# LTC6804-2_8S_TR-2512.net
KiCad netlist of a schematic drawn in Altium Designer
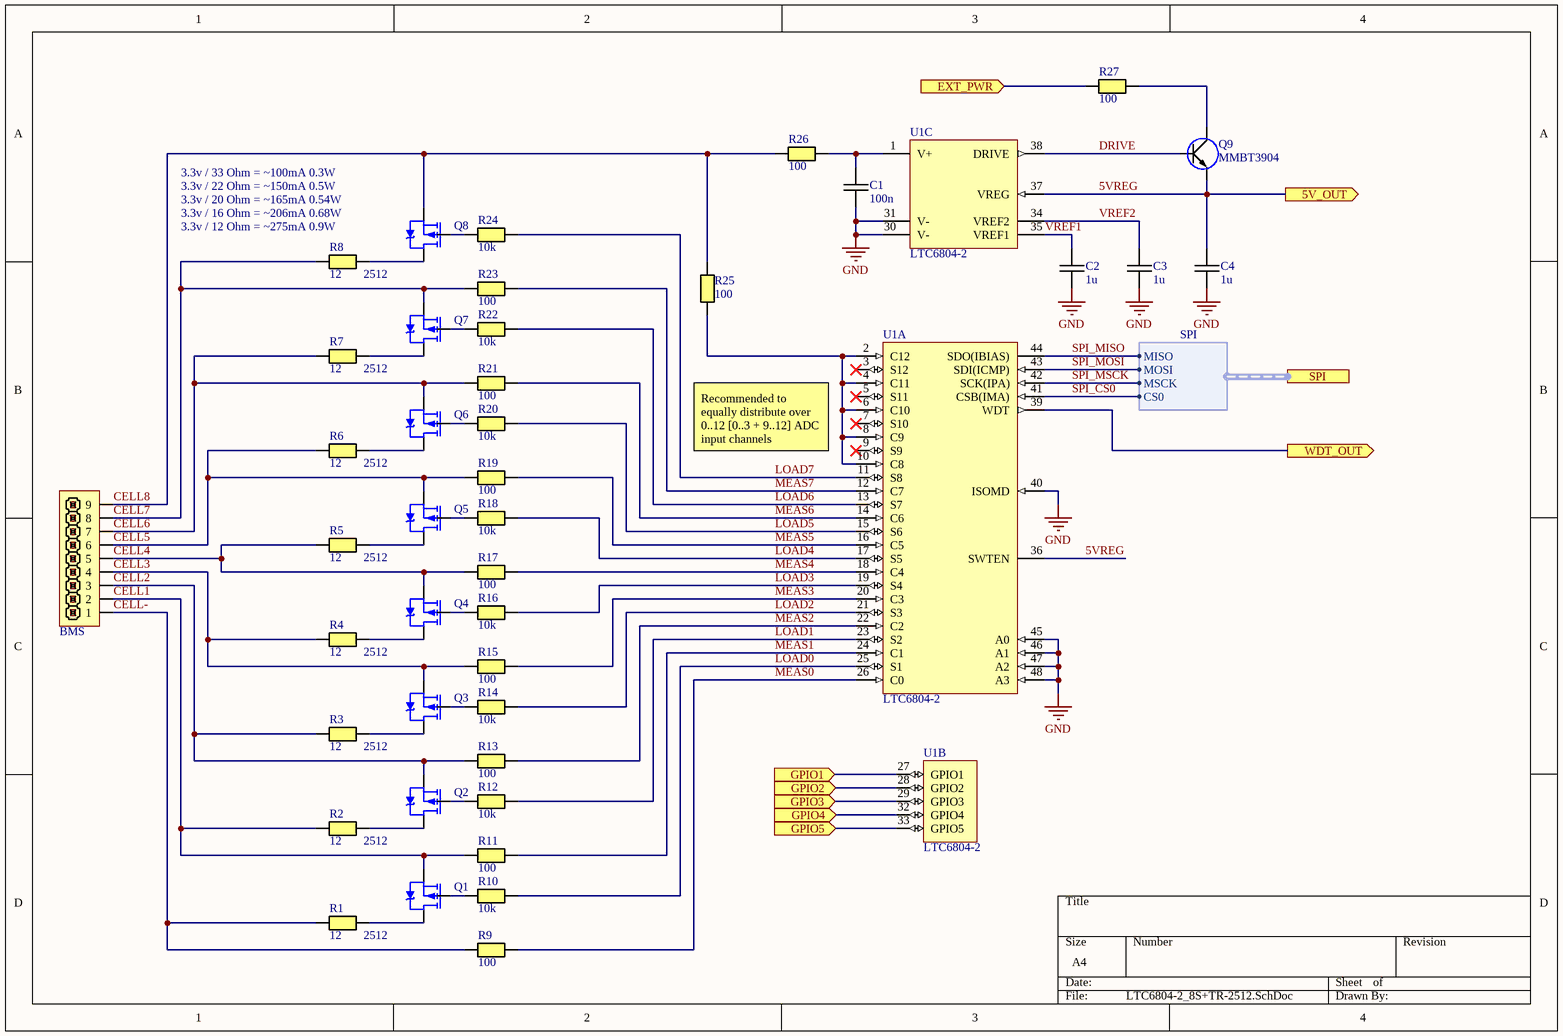
[diagram p0: LTC6804-2_8S+TR-2512.SchDoc]

(export (version "E")
  (design (tool "Eeschema 10.0.6"))
  (components
    (comp (ref "BMS")
      (value "PIN HEADER 1x9")
      (footprint "XH2.54 9P")
      (libsource (lib "Connectors") (part "PIN HEADER 2.54 1x9"))
    )
    (comp (ref "C1")
      (value "100n")
      (footprint "CAPC0603(1608)55_N")
      (description "Ceramic capacitor Medium density")
      (libsource (lib "Discrete") (part "Capacitor M"))
    )
    (comp (ref "C2")
      (value "1u")
      (footprint "CAPC0805(2012)75_N")
      (description "Ceramic capacitor Medium density")
      (libsource (lib "Discrete") (part "Capacitor M"))
    )
    (comp (ref "C3")
      (value "1u")
      (footprint "CAPC0805(2012)75_N")
      (description "Ceramic capacitor Medium density")
      (libsource (lib "Discrete") (part "Capacitor M"))
    )
    (comp (ref "C4")
      (value "1u")
      (footprint "CAPC0805(2012)75_N")
      (description "Ceramic capacitor Medium density")
      (libsource (lib "Discrete") (part "Capacitor M"))
    )
    (comp (ref "Q1")
      (value "BSS308PE")
      (footprint "SOT23")
      (description "OptiMOS™ P3 Small-Signal-Transistor")
      (libsource (lib "Transistors") (part "BSS308PE"))
    )
    (comp (ref "Q2")
      (value "BSS308PE")
      (footprint "SOT23")
      (description "OptiMOS™ P3 Small-Signal-Transistor")
      (libsource (lib "Transistors") (part "BSS308PE"))
    )
    (comp (ref "Q3")
      (value "BSS308PE")
      (footprint "SOT23")
      (description "OptiMOS™ P3 Small-Signal-Transistor")
      (libsource (lib "Transistors") (part "BSS308PE"))
    )
    (comp (ref "Q4")
      (value "BSS308PE")
      (footprint "SOT23")
      (description "OptiMOS™ P3 Small-Signal-Transistor")
      (libsource (lib "Transistors") (part "BSS308PE"))
    )
    (comp (ref "Q5")
      (value "BSS308PE")
      (footprint "SOT23")
      (description "OptiMOS™ P3 Small-Signal-Transistor")
      (libsource (lib "Transistors") (part "BSS308PE"))
    )
    (comp (ref "Q6")
      (value "BSS308PE")
      (footprint "SOT23")
      (description "OptiMOS™ P3 Small-Signal-Transistor")
      (libsource (lib "Transistors") (part "BSS308PE"))
    )
    (comp (ref "Q7")
      (value "BSS308PE")
      (footprint "SOT23")
      (description "OptiMOS™ P3 Small-Signal-Transistor")
      (libsource (lib "Transistors") (part "BSS308PE"))
    )
    (comp (ref "Q8")
      (value "BSS308PE")
      (footprint "SOT23")
      (description "OptiMOS™ P3 Small-Signal-Transistor")
      (libsource (lib "Transistors") (part "BSS308PE"))
    )
    (comp (ref "Q9")
      (value "MMBT3904")
      (footprint "SOT23")
      (description "NPN General Purpose Transistor")
      (libsource (lib "Transistors") (part "2N3904"))
    )
    (comp (ref "R1")
      (value "12")
      (footprint "RESC2512(6432)_N")
      (description "Resistor Medium Density")
      (fields (field (name "PACK") "2512"))
      (libsource (lib "") (part "Resistor M_1"))
    )
    (comp (ref "R2")
      (value "12")
      (footprint "RESC2512(6432)_N")
      (description "Resistor Medium Density")
      (fields (field (name "PACK") "2512"))
      (libsource (lib "") (part "Resistor M_1"))
    )
    (comp (ref "R3")
      (value "12")
      (footprint "RESC2512(6432)_N")
      (description "Resistor Medium Density")
      (fields (field (name "PACK") "2512"))
      (libsource (lib "") (part "Resistor M_1"))
    )
    (comp (ref "R4")
      (value "12")
      (footprint "RESC2512(6432)_N")
      (description "Resistor Medium Density")
      (fields (field (name "PACK") "2512"))
      (libsource (lib "") (part "Resistor M_1"))
    )
    (comp (ref "R5")
      (value "12")
      (footprint "RESC2512(6432)_N")
      (description "Resistor Medium Density")
      (fields (field (name "PACK") "2512"))
      (libsource (lib "") (part "Resistor M_1"))
    )
    (comp (ref "R6")
      (value "12")
      (footprint "RESC2512(6432)_N")
      (description "Resistor Medium Density")
      (fields (field (name "PACK") "2512"))
      (libsource (lib "") (part "Resistor M_1"))
    )
    (comp (ref "R7")
      (value "12")
      (footprint "RESC2512(6432)_N")
      (description "Resistor Medium Density")
      (fields (field (name "PACK") "2512"))
      (libsource (lib "") (part "Resistor M_1"))
    )
    (comp (ref "R8")
      (value "12")
      (footprint "RESC2512(6432)_N")
      (description "Resistor Medium Density")
      (fields (field (name "PACK") "2512"))
      (libsource (lib "") (part "Resistor M_1"))
    )
    (comp (ref "R9")
      (value "100")
      (footprint "RESC0603(1608)_N")
      (description "Resistor Medium Density")
      (libsource (lib "Discrete") (part "Resistor M"))
    )
    (comp (ref "R10")
      (value "10k")
      (footprint "RESC0603(1608)_N")
      (description "Resistor Medium Density")
      (libsource (lib "") (part "Resistor M_1"))
    )
    (comp (ref "R11")
      (value "100")
      (footprint "RESC0603(1608)_N")
      (description "Resistor Medium Density")
      (libsource (lib "Discrete") (part "Resistor M"))
    )
    (comp (ref "R12")
      (value "10k")
      (footprint "RESC0603(1608)_N")
      (description "Resistor Medium Density")
      (libsource (lib "") (part "Resistor M_1"))
    )
    (comp (ref "R13")
      (value "100")
      (footprint "RESC0603(1608)_N")
      (description "Resistor Medium Density")
      (libsource (lib "Discrete") (part "Resistor M"))
    )
    (comp (ref "R14")
      (value "10k")
      (footprint "RESC0603(1608)_N")
      (description "Resistor Medium Density")
      (libsource (lib "") (part "Resistor M_1"))
    )
    (comp (ref "R15")
      (value "100")
      (footprint "RESC0603(1608)_N")
      (description "Resistor Medium Density")
      (libsource (lib "Discrete") (part "Resistor M"))
    )
    (comp (ref "R16")
      (value "10k")
      (footprint "RESC0603(1608)_N")
      (description "Resistor Medium Density")
      (libsource (lib "") (part "Resistor M_1"))
    )
    (comp (ref "R17")
      (value "100")
      (footprint "RESC0603(1608)_N")
      (description "Resistor Medium Density")
      (libsource (lib "Discrete") (part "Resistor M"))
    )
    (comp (ref "R18")
      (value "10k")
      (footprint "RESC0603(1608)_N")
      (description "Resistor Medium Density")
      (libsource (lib "") (part "Resistor M_1"))
    )
    (comp (ref "R19")
      (value "100")
      (footprint "RESC0603(1608)_N")
      (description "Resistor Medium Density")
      (libsource (lib "Discrete") (part "Resistor M"))
    )
    (comp (ref "R20")
      (value "10k")
      (footprint "RESC0603(1608)_N")
      (description "Resistor Medium Density")
      (libsource (lib "") (part "Resistor M_1"))
    )
    (comp (ref "R21")
      (value "100")
      (footprint "RESC0603(1608)_N")
      (description "Resistor Medium Density")
      (libsource (lib "Discrete") (part "Resistor M"))
    )
    (comp (ref "R22")
      (value "10k")
      (footprint "RESC0603(1608)_N")
      (description "Resistor Medium Density")
      (libsource (lib "") (part "Resistor M_1"))
    )
    (comp (ref "R23")
      (value "100")
      (footprint "RESC0603(1608)_N")
      (description "Resistor Medium Density")
      (libsource (lib "Discrete") (part "Resistor M"))
    )
    (comp (ref "R24")
      (value "10k")
      (footprint "RESC0603(1608)_N")
      (description "Resistor Medium Density")
      (libsource (lib "") (part "Resistor M_1"))
    )
    (comp (ref "R25")
      (value "100")
      (footprint "RESC0603(1608)_N")
      (description "Resistor Medium Density")
      (libsource (lib "") (part "Resistor M_2"))
    )
    (comp (ref "R26")
      (value "100")
      (footprint "RESC0603(1608)_N")
      (description "Resistor Medium Density")
      (libsource (lib "Discrete") (part "Resistor M"))
    )
    (comp (ref "R27")
      (value "100")
      (footprint "RESC0805(2012)_N")
      (description "Resistor Medium Density")
      (libsource (lib "Discrete") (part "Resistor M"))
    )
    (comp (ref "U1")
      (value "LTC6804-2")
      (footprint "SSOP48")
      (libsource (lib "IntegrationCircuits") (part "LTC6804-2"))
    )
  )
  (nets
    (net (code "2") (name "/5VREG") (class "Default")
      (node (ref "C4") (pin "1") (pinfunction "1_1") (pintype "passive"))
      (node (ref "Q9") (pin "2") (pinfunction "E_2") (pintype "passive"))
      (node (ref "U1") (pin "36") (pinfunction "SWTEN_36") (pintype "passive"))
      (node (ref "U1") (pin "37") (pinfunction "VREG_37") (pintype "input"))
    )
    (net (code "3") (name "/CELL-") (class "Default")
      (node (ref "BMS") (pin "1") (pinfunction "1_1") (pintype "passive"))
      (node (ref "R1") (pin "1") (pinfunction "1_1") (pintype "passive"))
      (node (ref "R9") (pin "1") (pinfunction "1_1") (pintype "passive"))
    )
    (net (code "4") (name "/CELL1") (class "Default")
      (node (ref "BMS") (pin "2") (pinfunction "2_2") (pintype "passive"))
      (node (ref "Q1") (pin "2") (pinfunction "2_2") (pintype "passive"))
      (node (ref "R11") (pin "1") (pinfunction "1_1") (pintype "passive"))
      (node (ref "R2") (pin "1") (pinfunction "1_1") (pintype "passive"))
    )
    (net (code "5") (name "/CELL2") (class "Default")
      (node (ref "BMS") (pin "3") (pinfunction "3_3") (pintype "passive"))
      (node (ref "Q2") (pin "2") (pinfunction "2_2") (pintype "passive"))
      (node (ref "R13") (pin "1") (pinfunction "1_1") (pintype "passive"))
      (node (ref "R3") (pin "1") (pinfunction "1_1") (pintype "passive"))
    )
    (net (code "6") (name "/CELL3") (class "Default")
      (node (ref "BMS") (pin "4") (pinfunction "4_4") (pintype "passive"))
      (node (ref "Q3") (pin "2") (pinfunction "2_2") (pintype "passive"))
      (node (ref "R15") (pin "1") (pinfunction "1_1") (pintype "passive"))
      (node (ref "R4") (pin "1") (pinfunction "1_1") (pintype "passive"))
    )
    (net (code "7") (name "/CELL4") (class "Default")
      (node (ref "BMS") (pin "5") (pinfunction "5_5") (pintype "passive"))
      (node (ref "Q4") (pin "2") (pinfunction "2_2") (pintype "passive"))
      (node (ref "R17") (pin "1") (pinfunction "1_1") (pintype "passive"))
      (node (ref "R5") (pin "1") (pinfunction "1_1") (pintype "passive"))
    )
    (net (code "8") (name "/CELL5") (class "Default")
      (node (ref "BMS") (pin "6") (pinfunction "6_6") (pintype "passive"))
      (node (ref "Q5") (pin "2") (pinfunction "2_2") (pintype "passive"))
      (node (ref "R19") (pin "1") (pinfunction "1_1") (pintype "passive"))
      (node (ref "R6") (pin "1") (pinfunction "1_1") (pintype "passive"))
    )
    (net (code "9") (name "/CELL6") (class "Default")
      (node (ref "BMS") (pin "7") (pinfunction "7_7") (pintype "passive"))
      (node (ref "Q6") (pin "2") (pinfunction "2_2") (pintype "passive"))
      (node (ref "R21") (pin "1") (pinfunction "1_1") (pintype "passive"))
      (node (ref "R7") (pin "1") (pinfunction "1_1") (pintype "passive"))
    )
    (net (code "10") (name "/CELL7") (class "Default")
      (node (ref "BMS") (pin "8") (pinfunction "8_8") (pintype "passive"))
      (node (ref "Q7") (pin "2") (pinfunction "2_2") (pintype "passive"))
      (node (ref "R23") (pin "1") (pinfunction "1_1") (pintype "passive"))
      (node (ref "R8") (pin "1") (pinfunction "1_1") (pintype "passive"))
    )
    (net (code "11") (name "/CELL8") (class "Default")
      (node (ref "BMS") (pin "9") (pinfunction "9_9") (pintype "passive"))
      (node (ref "Q8") (pin "2") (pinfunction "2_2") (pintype "passive"))
      (node (ref "R25") (pin "1") (pinfunction "1_1") (pintype "passive"))
      (node (ref "R26") (pin "1") (pinfunction "1_1") (pintype "passive"))
    )
    (net (code "12") (name "/DRIVE") (class "Default")
      (node (ref "Q9") (pin "1") (pinfunction "B_1") (pintype "passive"))
      (node (ref "U1") (pin "38") (pinfunction "DRIVE_38") (pintype "output"))
    )
    (net (code "13") (name "/EXT_PWR") (class "Default")
      (node (ref "R27") (pin "1") (pinfunction "1_1") (pintype "passive"))
    )
    (net (code "14") (name "/GPIO1") (class "Default")
      (node (ref "U1") (pin "27") (pinfunction "GPIO1_27") (pintype "bidirectional"))
    )
    (net (code "15") (name "/GPIO2") (class "Default")
      (node (ref "U1") (pin "28") (pinfunction "GPIO2_28") (pintype "bidirectional"))
    )
    (net (code "16") (name "/GPIO3") (class "Default")
      (node (ref "U1") (pin "29") (pinfunction "GPIO3_29") (pintype "bidirectional"))
    )
    (net (code "17") (name "/GPIO4") (class "Default")
      (node (ref "U1") (pin "32") (pinfunction "GPIO4_32") (pintype "bidirectional"))
    )
    (net (code "18") (name "/GPIO5") (class "Default")
      (node (ref "U1") (pin "33") (pinfunction "GPIO5_33") (pintype "bidirectional"))
    )
    (net (code "19") (name "/LOAD0") (class "Default")
      (node (ref "R10") (pin "2") (pinfunction "2_2") (pintype "passive"))
      (node (ref "U1") (pin "25") (pinfunction "S1_25") (pintype "bidirectional"))
    )
    (net (code "20") (name "/LOAD1") (class "Default")
      (node (ref "R12") (pin "2") (pinfunction "2_2") (pintype "passive"))
      (node (ref "U1") (pin "23") (pinfunction "S2_23") (pintype "bidirectional"))
    )
    (net (code "21") (name "/LOAD2") (class "Default")
      (node (ref "R14") (pin "2") (pinfunction "2_2") (pintype "passive"))
      (node (ref "U1") (pin "21") (pinfunction "S3_21") (pintype "bidirectional"))
    )
    (net (code "22") (name "/LOAD3") (class "Default")
      (node (ref "R16") (pin "2") (pinfunction "2_2") (pintype "passive"))
      (node (ref "U1") (pin "19") (pinfunction "S4_19") (pintype "bidirectional"))
    )
    (net (code "23") (name "/LOAD4") (class "Default")
      (node (ref "R18") (pin "2") (pinfunction "2_2") (pintype "passive"))
      (node (ref "U1") (pin "17") (pinfunction "S5_17") (pintype "bidirectional"))
    )
    (net (code "24") (name "/LOAD5") (class "Default")
      (node (ref "R20") (pin "2") (pinfunction "2_2") (pintype "passive"))
      (node (ref "U1") (pin "15") (pinfunction "S6_15") (pintype "bidirectional"))
    )
    (net (code "25") (name "/LOAD6") (class "Default")
      (node (ref "R22") (pin "2") (pinfunction "2_2") (pintype "passive"))
      (node (ref "U1") (pin "13") (pinfunction "S7_13") (pintype "bidirectional"))
    )
    (net (code "26") (name "/LOAD7") (class "Default")
      (node (ref "R24") (pin "2") (pinfunction "2_2") (pintype "passive"))
      (node (ref "U1") (pin "11") (pinfunction "S8_11") (pintype "bidirectional"))
    )
    (net (code "27") (name "/MEAS0") (class "Default")
      (node (ref "R9") (pin "2") (pinfunction "2_2") (pintype "passive"))
      (node (ref "U1") (pin "26") (pinfunction "C0_26") (pintype "input"))
    )
    (net (code "28") (name "/MEAS1") (class "Default")
      (node (ref "R11") (pin "2") (pinfunction "2_2") (pintype "passive"))
      (node (ref "U1") (pin "24") (pinfunction "C1_24") (pintype "input"))
    )
    (net (code "29") (name "/MEAS2") (class "Default")
      (node (ref "R13") (pin "2") (pinfunction "2_2") (pintype "passive"))
      (node (ref "U1") (pin "22") (pinfunction "C2_22") (pintype "input"))
    )
    (net (code "30") (name "/MEAS3") (class "Default")
      (node (ref "R15") (pin "2") (pinfunction "2_2") (pintype "passive"))
      (node (ref "U1") (pin "20") (pinfunction "C3_20") (pintype "input"))
    )
    (net (code "31") (name "/MEAS4") (class "Default")
      (node (ref "R17") (pin "2") (pinfunction "2_2") (pintype "passive"))
      (node (ref "U1") (pin "18") (pinfunction "C4_18") (pintype "input"))
    )
    (net (code "32") (name "/MEAS5") (class "Default")
      (node (ref "R19") (pin "2") (pinfunction "2_2") (pintype "passive"))
      (node (ref "U1") (pin "16") (pinfunction "C5_16") (pintype "input"))
    )
    (net (code "33") (name "/MEAS6") (class "Default")
      (node (ref "R21") (pin "2") (pinfunction "2_2") (pintype "passive"))
      (node (ref "U1") (pin "14") (pinfunction "C6_14") (pintype "input"))
    )
    (net (code "34") (name "/MEAS7") (class "Default")
      (node (ref "R23") (pin "2") (pinfunction "2_2") (pintype "passive"))
      (node (ref "U1") (pin "12") (pinfunction "C7_12") (pintype "input"))
    )
    (net (code "35") (name "/SPI_CS0") (class "Default")
      (node (ref "U1") (pin "41") (pinfunction "CSB(IMA)_41") (pintype "input"))
    )
    (net (code "36") (name "/SPI_MISO") (class "Default")
      (node (ref "U1") (pin "44") (pinfunction "SDO(IBIAS)_44") (pintype "open_collector"))
    )
    (net (code "37") (name "/SPI_MOSI") (class "Default")
      (node (ref "U1") (pin "43") (pinfunction "SDI(ICMP)_43") (pintype "input"))
    )
    (net (code "38") (name "/SPI_MSCK") (class "Default")
      (node (ref "U1") (pin "42") (pinfunction "SCK(IPA)_42") (pintype "input"))
    )
    (net (code "39") (name "/VREF1") (class "Default")
      (node (ref "C2") (pin "1") (pinfunction "1_1") (pintype "passive"))
      (node (ref "U1") (pin "35") (pinfunction "VREF1_35") (pintype "power_in"))
    )
    (net (code "40") (name "/VREF2") (class "Default")
      (node (ref "C3") (pin "1") (pinfunction "1_1") (pintype "passive"))
      (node (ref "U1") (pin "34") (pinfunction "VREF2_34") (pintype "power_in"))
    )
    (net (code "41") (name "/WDT_OUT") (class "Default")
      (node (ref "U1") (pin "39") (pinfunction "WDT_39") (pintype "output"))
    )
    (net (code "43") (name "GND") (class "Default")
      (node (ref "C1") (pin "2") (pinfunction "2_2") (pintype "passive"))
      (node (ref "C2") (pin "2") (pinfunction "2_2") (pintype "passive"))
      (node (ref "C3") (pin "2") (pinfunction "2_2") (pintype "passive"))
      (node (ref "C4") (pin "2") (pinfunction "2_2") (pintype "passive"))
      (node (ref "U1") (pin "30") (pinfunction "V-_30") (pintype "power_in"))
      (node (ref "U1") (pin "31") (pinfunction "V-_31") (pintype "power_in"))
      (node (ref "U1") (pin "40") (pinfunction "ISOMD_40") (pintype "input"))
      (node (ref "U1") (pin "45") (pinfunction "A0_45") (pintype "input"))
      (node (ref "U1") (pin "46") (pinfunction "A1_46") (pintype "input"))
      (node (ref "U1") (pin "47") (pinfunction "A2_47") (pintype "input"))
      (node (ref "U1") (pin "48") (pinfunction "A3_48") (pintype "input"))
    )
    (net (code "44") (name "Net-(Q1-Pad1)") (class "Default")
      (node (ref "Q1") (pin "1") (pinfunction "1_1") (pintype "passive"))
      (node (ref "R10") (pin "1") (pinfunction "1_1") (pintype "passive"))
    )
    (net (code "45") (name "Net-(Q1-Pad3)") (class "Default")
      (node (ref "Q1") (pin "3") (pinfunction "3_3") (pintype "passive"))
      (node (ref "R1") (pin "2") (pinfunction "2_2") (pintype "passive"))
    )
    (net (code "46") (name "Net-(Q2-Pad1)") (class "Default")
      (node (ref "Q2") (pin "1") (pinfunction "1_1") (pintype "passive"))
      (node (ref "R12") (pin "1") (pinfunction "1_1") (pintype "passive"))
    )
    (net (code "47") (name "Net-(Q2-Pad3)") (class "Default")
      (node (ref "Q2") (pin "3") (pinfunction "3_3") (pintype "passive"))
      (node (ref "R2") (pin "2") (pinfunction "2_2") (pintype "passive"))
    )
    (net (code "48") (name "Net-(Q3-Pad1)") (class "Default")
      (node (ref "Q3") (pin "1") (pinfunction "1_1") (pintype "passive"))
      (node (ref "R14") (pin "1") (pinfunction "1_1") (pintype "passive"))
    )
    (net (code "49") (name "Net-(Q3-Pad3)") (class "Default")
      (node (ref "Q3") (pin "3") (pinfunction "3_3") (pintype "passive"))
      (node (ref "R3") (pin "2") (pinfunction "2_2") (pintype "passive"))
    )
    (net (code "50") (name "Net-(Q4-Pad1)") (class "Default")
      (node (ref "Q4") (pin "1") (pinfunction "1_1") (pintype "passive"))
      (node (ref "R16") (pin "1") (pinfunction "1_1") (pintype "passive"))
    )
    (net (code "51") (name "Net-(Q4-Pad3)") (class "Default")
      (node (ref "Q4") (pin "3") (pinfunction "3_3") (pintype "passive"))
      (node (ref "R4") (pin "2") (pinfunction "2_2") (pintype "passive"))
    )
    (net (code "52") (name "Net-(Q5-Pad1)") (class "Default")
      (node (ref "Q5") (pin "1") (pinfunction "1_1") (pintype "passive"))
      (node (ref "R18") (pin "1") (pinfunction "1_1") (pintype "passive"))
    )
    (net (code "53") (name "Net-(Q5-Pad3)") (class "Default")
      (node (ref "Q5") (pin "3") (pinfunction "3_3") (pintype "passive"))
      (node (ref "R5") (pin "2") (pinfunction "2_2") (pintype "passive"))
    )
    (net (code "54") (name "Net-(Q6-Pad1)") (class "Default")
      (node (ref "Q6") (pin "1") (pinfunction "1_1") (pintype "passive"))
      (node (ref "R20") (pin "1") (pinfunction "1_1") (pintype "passive"))
    )
    (net (code "55") (name "Net-(Q6-Pad3)") (class "Default")
      (node (ref "Q6") (pin "3") (pinfunction "3_3") (pintype "passive"))
      (node (ref "R6") (pin "2") (pinfunction "2_2") (pintype "passive"))
    )
    (net (code "56") (name "Net-(Q7-Pad1)") (class "Default")
      (node (ref "Q7") (pin "1") (pinfunction "1_1") (pintype "passive"))
      (node (ref "R22") (pin "1") (pinfunction "1_1") (pintype "passive"))
    )
    (net (code "57") (name "Net-(Q7-Pad3)") (class "Default")
      (node (ref "Q7") (pin "3") (pinfunction "3_3") (pintype "passive"))
      (node (ref "R7") (pin "2") (pinfunction "2_2") (pintype "passive"))
    )
    (net (code "58") (name "Net-(Q8-Pad1)") (class "Default")
      (node (ref "Q8") (pin "1") (pinfunction "1_1") (pintype "passive"))
      (node (ref "R24") (pin "1") (pinfunction "1_1") (pintype "passive"))
    )
    (net (code "59") (name "Net-(Q8-Pad3)") (class "Default")
      (node (ref "Q8") (pin "3") (pinfunction "3_3") (pintype "passive"))
      (node (ref "R8") (pin "2") (pinfunction "2_2") (pintype "passive"))
    )
    (net (code "60") (name "Net-(Q9-C)") (class "Default")
      (node (ref "Q9") (pin "3") (pinfunction "C_3") (pintype "passive"))
      (node (ref "R27") (pin "2") (pinfunction "2_2") (pintype "passive"))
    )
    (net (code "61") (name "Net-(U1A-C10)") (class "Default")
      (node (ref "R25") (pin "2") (pinfunction "2_2") (pintype "passive"))
      (node (ref "U1") (pin "10") (pinfunction "C8_10") (pintype "input"))
      (node (ref "U1") (pin "2") (pinfunction "C12_2") (pintype "input"))
      (node (ref "U1") (pin "4") (pinfunction "C11_4") (pintype "input"))
      (node (ref "U1") (pin "6") (pinfunction "C10_6") (pintype "input"))
      (node (ref "U1") (pin "8") (pinfunction "C9_8") (pintype "input"))
    )
    (net (code "62") (name "Net-(U1C-V+)") (class "Default")
      (node (ref "C1") (pin "1") (pinfunction "1_1") (pintype "passive"))
      (node (ref "R26") (pin "2") (pinfunction "2_2") (pintype "passive"))
      (node (ref "U1") (pin "1") (pinfunction "V+_1") (pintype "power_in"))
    )
    (net (code "63") (name "unconnected-(U1A-S9-Pad9)") (class "Default")
      (node (ref "U1") (pin "9") (pinfunction "S9_9") (pintype "bidirectional+no_connect"))
    )
    (net (code "64") (name "unconnected-(U1A-S10-Pad7)") (class "Default")
      (node (ref "U1") (pin "7") (pinfunction "S10_7") (pintype "bidirectional+no_connect"))
    )
    (net (code "65") (name "unconnected-(U1A-S11-Pad5)") (class "Default")
      (node (ref "U1") (pin "5") (pinfunction "S11_5") (pintype "bidirectional+no_connect"))
    )
    (net (code "66") (name "unconnected-(U1A-S12-Pad3)") (class "Default")
      (node (ref "U1") (pin "3") (pinfunction "S12_3") (pintype "bidirectional+no_connect"))
    )
  )
)
